# NixieTerm.net
KiCad netlist of a schematic drawn in EAGLE
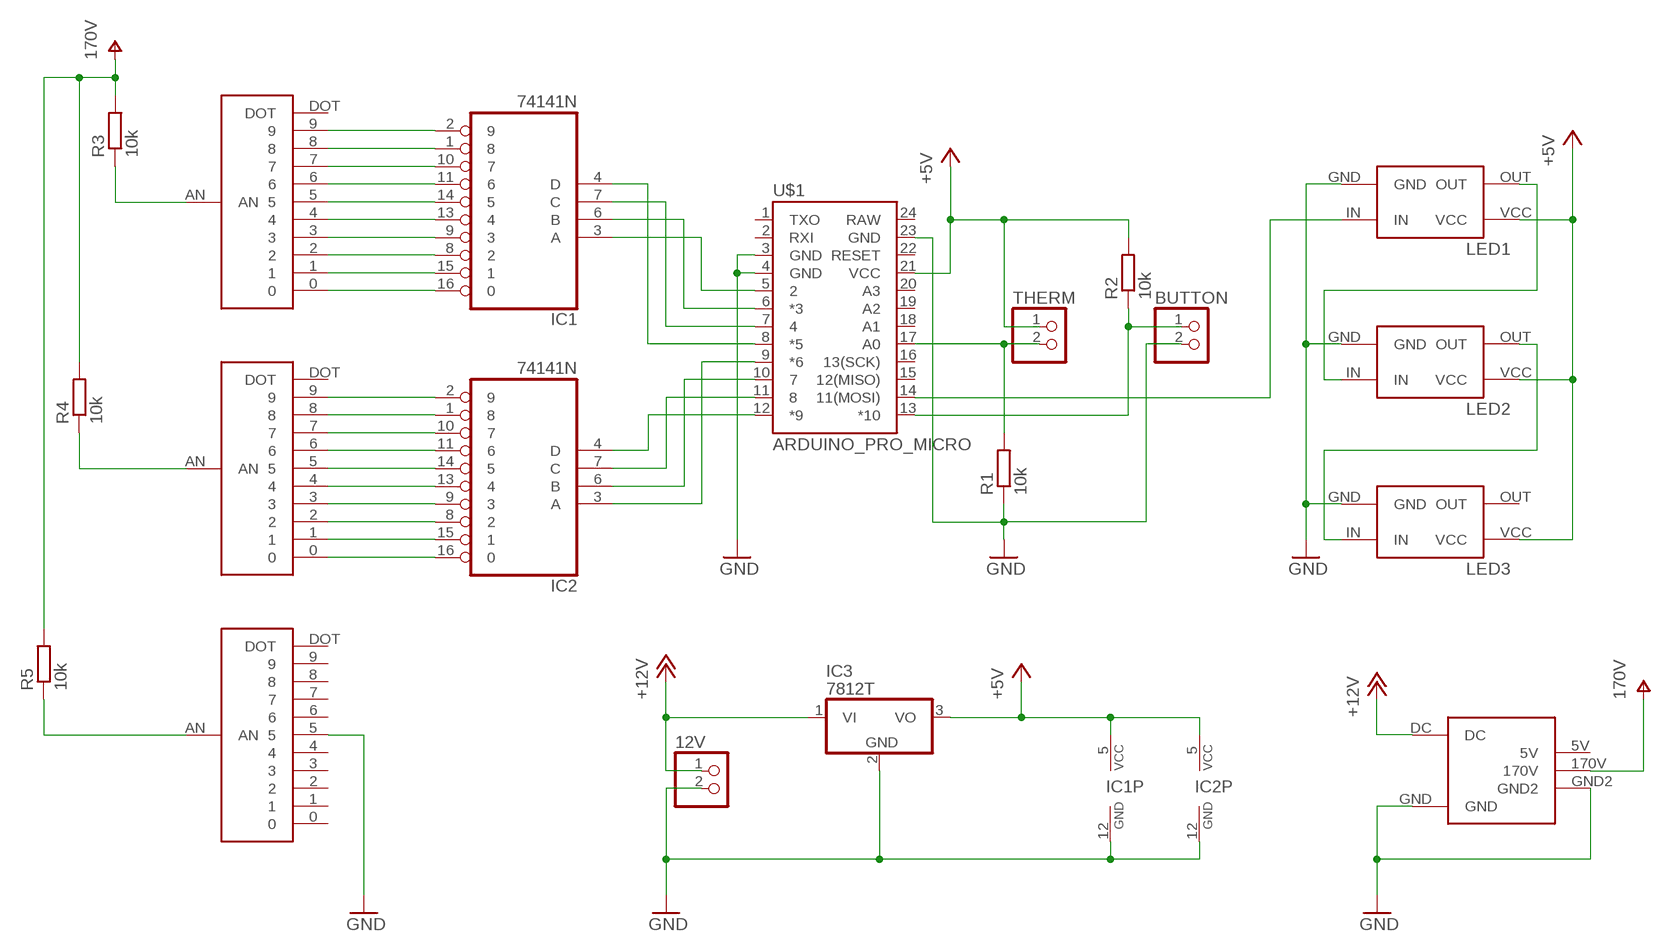
[diagram p0: schematic, sheet 1]

(export (version "E")
  (design (tool "Eeschema 10.0.6"))
  (components
    (comp (ref "12V")
      (value "PINHD-1X2")
      (footprint "eagle-import:1X02")
      (libsource (lib "eagle-import") (part "PINHD-1X2"))
    )
    (comp (ref "BUTTON")
      (value "PINHD-1X2")
      (footprint "eagle-import:1X02")
      (libsource (lib "eagle-import") (part "PINHD-1X2"))
    )
    (comp (ref "DEC")
      (value "NIXIE-SOCKET")
      (footprint "eagle-import:NIXIE-SOCKET-PAC")
      (libsource (lib "eagle-import") (part "NIXIE-SOCKET"))
    )
    (comp (ref "IC1")
      (value "74141N")
      (footprint "eagle-import:DIL16")
      (libsource (lib "eagle-import") (part "74141N"))
    )
    (comp (ref "IC2")
      (value "74141N")
      (footprint "eagle-import:DIL16")
      (libsource (lib "eagle-import") (part "74141N"))
    )
    (comp (ref "IC3")
      (value "7812T")
      (footprint "eagle-import:TO220H")
      (libsource (lib "eagle-import") (part "78T12"))
    )
    (comp (ref "LED1")
      (value "WS2812-LED")
      (footprint "eagle-import:WS2812-LED-PAC")
      (libsource (lib "eagle-import") (part "WS2812-LED"))
    )
    (comp (ref "LED2")
      (value "WS2812-LED")
      (footprint "eagle-import:WS2812-LED-PAC")
      (libsource (lib "eagle-import") (part "WS2812-LED"))
    )
    (comp (ref "LED3")
      (value "WS2812-LED")
      (footprint "eagle-import:WS2812-LED-PAC")
      (libsource (lib "eagle-import") (part "WS2812-LED"))
    )
    (comp (ref "R1")
      (value "10k")
      (footprint "eagle-import:0207_12")
      (libsource (lib "eagle-import") (part "R-EU_0207/12"))
    )
    (comp (ref "R2")
      (value "10k")
      (footprint "eagle-import:0207_12")
      (libsource (lib "eagle-import") (part "R-EU_0207/12"))
    )
    (comp (ref "R3")
      (value "10k")
      (footprint "eagle-import:0207_12")
      (libsource (lib "eagle-import") (part "R-EU_0207/12"))
    )
    (comp (ref "R4")
      (value "10k")
      (footprint "eagle-import:0207_12")
      (libsource (lib "eagle-import") (part "R-EU_0207/12"))
    )
    (comp (ref "R5")
      (value "10k")
      (footprint "eagle-import:0207_12")
      (libsource (lib "eagle-import") (part "R-EU_0207/12"))
    )
    (comp (ref "SYM")
      (value "NIXIE-SOCKET")
      (footprint "eagle-import:NIXIE-SOCKET-PAC")
      (libsource (lib "eagle-import") (part "NIXIE-SOCKET"))
    )
    (comp (ref "THERM")
      (value "PINHD-1X2")
      (footprint "eagle-import:1X02")
      (libsource (lib "eagle-import") (part "PINHD-1X2"))
    )
    (comp (ref "U$1")
      (value "ARDUINO_PRO_MICRO")
      (footprint "eagle-import:ARDUINO_PRO_MICRO")
      (libsource (lib "eagle-import") (part "ARDUINO_PRO_MICRO"))
    )
    (comp (ref "U$2")
      (value "NIXIE-SUPPLY")
      (footprint "eagle-import:NIXIE-SUPPLY-PAC")
      (libsource (lib "eagle-import") (part "NIXIE-SUPPLY"))
    )
    (comp (ref "UNIT")
      (value "NIXIE-SOCKET")
      (footprint "eagle-import:NIXIE-SOCKET-PAC")
      (libsource (lib "eagle-import") (part "NIXIE-SOCKET"))
    )
  )
  (nets
    (net (code "1") (name "+5V") (class "Default")
      (node (ref "IC1") (pin "5") (pinfunction "VCC_5") (pintype "power_in"))
      (node (ref "IC2") (pin "5") (pinfunction "VCC_5") (pintype "power_in"))
      (node (ref "IC3") (pin "3") (pinfunction "VO_3") (pintype "passive"))
      (node (ref "LED1") (pin "VCC") (pinfunction "VCC_VCC") (pintype "bidirectional"))
      (node (ref "LED2") (pin "VCC") (pinfunction "VCC_VCC") (pintype "bidirectional"))
      (node (ref "LED3") (pin "VCC") (pinfunction "VCC_VCC") (pintype "bidirectional"))
      (node (ref "R2") (pin "2") (pinfunction "2_2") (pintype "passive"))
      (node (ref "THERM") (pin "1") (pinfunction "1_1") (pintype "passive"))
      (node (ref "U$1") (pin "21") (pinfunction "VCC_21") (pintype "bidirectional"))
    )
    (net (code "2") (name "+12V") (class "Default")
      (node (ref "12V") (pin "1") (pinfunction "1_1") (pintype "passive"))
      (node (ref "IC3") (pin "1") (pinfunction "VI_1") (pintype "input"))
      (node (ref "U$2") (pin "DC") (pinfunction "DC_DC") (pintype "bidirectional"))
    )
    (net (code "3") (name "170V") (class "Default")
      (node (ref "R3") (pin "2") (pinfunction "2_2") (pintype "passive"))
      (node (ref "R4") (pin "2") (pinfunction "2_2") (pintype "passive"))
      (node (ref "R5") (pin "2") (pinfunction "2_2") (pintype "passive"))
      (node (ref "U$2") (pin "170V") (pinfunction "170V_170V") (pintype "bidirectional"))
    )
    (net (code "4") (name "GND") (class "Default")
      (node (ref "12V") (pin "2") (pinfunction "2_2") (pintype "passive"))
      (node (ref "BUTTON") (pin "2") (pinfunction "2_2") (pintype "passive"))
      (node (ref "IC1") (pin "12") (pinfunction "GND_12") (pintype "power_in"))
      (node (ref "IC2") (pin "12") (pinfunction "GND_12") (pintype "power_in"))
      (node (ref "IC3") (pin "2") (pinfunction "GND_2") (pintype "passive"))
      (node (ref "LED1") (pin "GND") (pinfunction "GND_GND") (pintype "bidirectional"))
      (node (ref "LED2") (pin "GND") (pinfunction "GND_GND") (pintype "bidirectional"))
      (node (ref "LED3") (pin "GND") (pinfunction "GND_GND") (pintype "bidirectional"))
      (node (ref "R1") (pin "1") (pinfunction "1_1") (pintype "passive"))
      (node (ref "SYM") (pin "5") (pinfunction "5_5") (pintype "bidirectional"))
      (node (ref "U$1") (pin "23") (pinfunction "GND_23") (pintype "bidirectional"))
      (node (ref "U$1") (pin "3") (pinfunction "GND_3") (pintype "bidirectional"))
      (node (ref "U$1") (pin "4") (pinfunction "GND_4") (pintype "bidirectional"))
      (node (ref "U$2") (pin "GND") (pinfunction "GND_GND") (pintype "bidirectional"))
      (node (ref "U$2") (pin "GND2") (pinfunction "GND2_GND2") (pintype "bidirectional"))
    )
    (net (code "5") (name "Net-(DEC-PadAN)") (class "Default")
      (node (ref "DEC") (pin "AN") (pinfunction "AN_AN") (pintype "bidirectional"))
      (node (ref "R3") (pin "1") (pinfunction "1_1") (pintype "passive"))
    )
    (net (code "6") (name "Net-(IC1A-0)") (class "Default")
      (node (ref "DEC") (pin "0") (pinfunction "0_0") (pintype "bidirectional"))
      (node (ref "IC1") (pin "16") (pinfunction "0_16") (pintype "open_collector"))
    )
    (net (code "7") (name "Net-(IC1A-1)") (class "Default")
      (node (ref "DEC") (pin "1") (pinfunction "1_1") (pintype "bidirectional"))
      (node (ref "IC1") (pin "15") (pinfunction "1_15") (pintype "open_collector"))
    )
    (net (code "8") (name "Net-(IC1A-2)") (class "Default")
      (node (ref "DEC") (pin "2") (pinfunction "2_2") (pintype "bidirectional"))
      (node (ref "IC1") (pin "8") (pinfunction "2_8") (pintype "open_collector"))
    )
    (net (code "9") (name "Net-(IC1A-3)") (class "Default")
      (node (ref "DEC") (pin "3") (pinfunction "3_3") (pintype "bidirectional"))
      (node (ref "IC1") (pin "9") (pinfunction "3_9") (pintype "open_collector"))
    )
    (net (code "10") (name "Net-(IC1A-4)") (class "Default")
      (node (ref "DEC") (pin "4") (pinfunction "4_4") (pintype "bidirectional"))
      (node (ref "IC1") (pin "13") (pinfunction "4_13") (pintype "open_collector"))
    )
    (net (code "11") (name "Net-(IC1A-5)") (class "Default")
      (node (ref "DEC") (pin "5") (pinfunction "5_5") (pintype "bidirectional"))
      (node (ref "IC1") (pin "14") (pinfunction "5_14") (pintype "open_collector"))
    )
    (net (code "12") (name "Net-(IC1A-6)") (class "Default")
      (node (ref "DEC") (pin "6") (pinfunction "6_6") (pintype "bidirectional"))
      (node (ref "IC1") (pin "11") (pinfunction "6_11") (pintype "open_collector"))
    )
    (net (code "13") (name "Net-(IC1A-7)") (class "Default")
      (node (ref "DEC") (pin "7") (pinfunction "7_7") (pintype "bidirectional"))
      (node (ref "IC1") (pin "10") (pinfunction "7_10") (pintype "open_collector"))
    )
    (net (code "14") (name "Net-(IC1A-8)") (class "Default")
      (node (ref "DEC") (pin "8") (pinfunction "8_8") (pintype "bidirectional"))
      (node (ref "IC1") (pin "1") (pinfunction "8_1") (pintype "open_collector"))
    )
    (net (code "15") (name "Net-(IC1A-9)") (class "Default")
      (node (ref "DEC") (pin "9") (pinfunction "9_9") (pintype "bidirectional"))
      (node (ref "IC1") (pin "2") (pinfunction "9_2") (pintype "open_collector"))
    )
    (net (code "16") (name "Net-(IC1A-A)") (class "Default")
      (node (ref "IC1") (pin "3") (pinfunction "A_3") (pintype "input"))
      (node (ref "U$1") (pin "5") (pinfunction "2_5") (pintype "bidirectional"))
    )
    (net (code "17") (name "Net-(IC1A-B)") (class "Default")
      (node (ref "IC1") (pin "6") (pinfunction "B_6") (pintype "input"))
      (node (ref "U$1") (pin "6") (pinfunction "*3_6") (pintype "bidirectional"))
    )
    (net (code "18") (name "Net-(IC1A-C)") (class "Default")
      (node (ref "IC1") (pin "7") (pinfunction "C_7") (pintype "input"))
      (node (ref "U$1") (pin "7") (pinfunction "4_7") (pintype "bidirectional"))
    )
    (net (code "19") (name "Net-(IC1A-D)") (class "Default")
      (node (ref "IC1") (pin "4") (pinfunction "D_4") (pintype "input"))
      (node (ref "U$1") (pin "8") (pinfunction "*5_8") (pintype "bidirectional"))
    )
    (net (code "20") (name "Net-(IC2A-0)") (class "Default")
      (node (ref "IC2") (pin "16") (pinfunction "0_16") (pintype "open_collector"))
      (node (ref "UNIT") (pin "0") (pinfunction "0_0") (pintype "bidirectional"))
    )
    (net (code "21") (name "Net-(IC2A-1)") (class "Default")
      (node (ref "IC2") (pin "15") (pinfunction "1_15") (pintype "open_collector"))
      (node (ref "UNIT") (pin "1") (pinfunction "1_1") (pintype "bidirectional"))
    )
    (net (code "22") (name "Net-(IC2A-2)") (class "Default")
      (node (ref "IC2") (pin "8") (pinfunction "2_8") (pintype "open_collector"))
      (node (ref "UNIT") (pin "2") (pinfunction "2_2") (pintype "bidirectional"))
    )
    (net (code "23") (name "Net-(IC2A-3)") (class "Default")
      (node (ref "IC2") (pin "9") (pinfunction "3_9") (pintype "open_collector"))
      (node (ref "UNIT") (pin "3") (pinfunction "3_3") (pintype "bidirectional"))
    )
    (net (code "24") (name "Net-(IC2A-4)") (class "Default")
      (node (ref "IC2") (pin "13") (pinfunction "4_13") (pintype "open_collector"))
      (node (ref "UNIT") (pin "4") (pinfunction "4_4") (pintype "bidirectional"))
    )
    (net (code "25") (name "Net-(IC2A-5)") (class "Default")
      (node (ref "IC2") (pin "14") (pinfunction "5_14") (pintype "open_collector"))
      (node (ref "UNIT") (pin "5") (pinfunction "5_5") (pintype "bidirectional"))
    )
    (net (code "26") (name "Net-(IC2A-6)") (class "Default")
      (node (ref "IC2") (pin "11") (pinfunction "6_11") (pintype "open_collector"))
      (node (ref "UNIT") (pin "6") (pinfunction "6_6") (pintype "bidirectional"))
    )
    (net (code "27") (name "Net-(IC2A-7)") (class "Default")
      (node (ref "IC2") (pin "10") (pinfunction "7_10") (pintype "open_collector"))
      (node (ref "UNIT") (pin "7") (pinfunction "7_7") (pintype "bidirectional"))
    )
    (net (code "28") (name "Net-(IC2A-8)") (class "Default")
      (node (ref "IC2") (pin "1") (pinfunction "8_1") (pintype "open_collector"))
      (node (ref "UNIT") (pin "8") (pinfunction "8_8") (pintype "bidirectional"))
    )
    (net (code "29") (name "Net-(IC2A-9)") (class "Default")
      (node (ref "IC2") (pin "2") (pinfunction "9_2") (pintype "open_collector"))
      (node (ref "UNIT") (pin "9") (pinfunction "9_9") (pintype "bidirectional"))
    )
    (net (code "30") (name "Net-(IC2A-A)") (class "Default")
      (node (ref "IC2") (pin "3") (pinfunction "A_3") (pintype "input"))
      (node (ref "U$1") (pin "9") (pinfunction "*6_9") (pintype "bidirectional"))
    )
    (net (code "31") (name "Net-(IC2A-B)") (class "Default")
      (node (ref "IC2") (pin "6") (pinfunction "B_6") (pintype "input"))
      (node (ref "U$1") (pin "10") (pinfunction "7_10") (pintype "bidirectional"))
    )
    (net (code "32") (name "Net-(IC2A-C)") (class "Default")
      (node (ref "IC2") (pin "7") (pinfunction "C_7") (pintype "input"))
      (node (ref "U$1") (pin "11") (pinfunction "8_11") (pintype "bidirectional"))
    )
    (net (code "33") (name "Net-(IC2A-D)") (class "Default")
      (node (ref "IC2") (pin "4") (pinfunction "D_4") (pintype "input"))
      (node (ref "U$1") (pin "12") (pinfunction "*9_12") (pintype "bidirectional"))
    )
    (net (code "34") (name "Net-(LED1-PadOUT)") (class "Default")
      (node (ref "LED1") (pin "OUT") (pinfunction "OUT_OUT") (pintype "bidirectional"))
      (node (ref "LED2") (pin "IN") (pinfunction "IN_IN") (pintype "bidirectional"))
    )
    (net (code "35") (name "Net-(LED2-PadOUT)") (class "Default")
      (node (ref "LED2") (pin "OUT") (pinfunction "OUT_OUT") (pintype "bidirectional"))
      (node (ref "LED3") (pin "IN") (pinfunction "IN_IN") (pintype "bidirectional"))
    )
    (net (code "36") (name "Net-(R4-Pad1)") (class "Default")
      (node (ref "R4") (pin "1") (pinfunction "1_1") (pintype "passive"))
      (node (ref "UNIT") (pin "AN") (pinfunction "AN_AN") (pintype "bidirectional"))
    )
    (net (code "37") (name "Net-(R5-Pad1)") (class "Default")
      (node (ref "R5") (pin "1") (pinfunction "1_1") (pintype "passive"))
      (node (ref "SYM") (pin "AN") (pinfunction "AN_AN") (pintype "bidirectional"))
    )
    (net (code "38") (name "Net-(U$1-*10)") (class "Default")
      (node (ref "BUTTON") (pin "1") (pinfunction "1_1") (pintype "passive"))
      (node (ref "R2") (pin "1") (pinfunction "1_1") (pintype "passive"))
      (node (ref "U$1") (pin "13") (pinfunction "*10_13") (pintype "bidirectional"))
    )
    (net (code "39") (name "Net-(U$1-11(MOSI))") (class "Default")
      (node (ref "LED1") (pin "IN") (pinfunction "IN_IN") (pintype "bidirectional"))
      (node (ref "U$1") (pin "14") (pinfunction "11(MOSI)_14") (pintype "bidirectional"))
    )
    (net (code "40") (name "Net-(U$1-A0)") (class "Default")
      (node (ref "R1") (pin "2") (pinfunction "2_2") (pintype "passive"))
      (node (ref "THERM") (pin "2") (pinfunction "2_2") (pintype "passive"))
      (node (ref "U$1") (pin "17") (pinfunction "A0_17") (pintype "bidirectional"))
    )
    (net (code "41") (name "unconnected-(DEC-PadDOT)") (class "Default")
      (node (ref "DEC") (pin "DOT") (pinfunction "DOT_DOT") (pintype "bidirectional"))
    )
    (net (code "42") (name "unconnected-(LED3-PadOUT)") (class "Default")
      (node (ref "LED3") (pin "OUT") (pinfunction "OUT_OUT") (pintype "bidirectional"))
    )
    (net (code "43") (name "unconnected-(SYM-Pad0)") (class "Default")
      (node (ref "SYM") (pin "0") (pinfunction "0_0") (pintype "bidirectional"))
    )
    (net (code "44") (name "unconnected-(SYM-Pad1)") (class "Default")
      (node (ref "SYM") (pin "1") (pinfunction "1_1") (pintype "bidirectional"))
    )
    (net (code "45") (name "unconnected-(SYM-Pad2)") (class "Default")
      (node (ref "SYM") (pin "2") (pinfunction "2_2") (pintype "bidirectional"))
    )
    (net (code "46") (name "unconnected-(SYM-Pad3)") (class "Default")
      (node (ref "SYM") (pin "3") (pinfunction "3_3") (pintype "bidirectional"))
    )
    (net (code "47") (name "unconnected-(SYM-Pad4)") (class "Default")
      (node (ref "SYM") (pin "4") (pinfunction "4_4") (pintype "bidirectional"))
    )
    (net (code "48") (name "unconnected-(SYM-Pad6)") (class "Default")
      (node (ref "SYM") (pin "6") (pinfunction "6_6") (pintype "bidirectional"))
    )
    (net (code "49") (name "unconnected-(SYM-Pad7)") (class "Default")
      (node (ref "SYM") (pin "7") (pinfunction "7_7") (pintype "bidirectional"))
    )
    (net (code "50") (name "unconnected-(SYM-Pad8)") (class "Default")
      (node (ref "SYM") (pin "8") (pinfunction "8_8") (pintype "bidirectional"))
    )
    (net (code "51") (name "unconnected-(SYM-Pad9)") (class "Default")
      (node (ref "SYM") (pin "9") (pinfunction "9_9") (pintype "bidirectional"))
    )
    (net (code "52") (name "unconnected-(SYM-PadDOT)") (class "Default")
      (node (ref "SYM") (pin "DOT") (pinfunction "DOT_DOT") (pintype "bidirectional"))
    )
    (net (code "53") (name "unconnected-(U$1-12(MISO)-Pad15)") (class "Default")
      (node (ref "U$1") (pin "15") (pinfunction "12(MISO)_15") (pintype "bidirectional"))
    )
    (net (code "54") (name "unconnected-(U$1-13(SCK)-Pad16)") (class "Default")
      (node (ref "U$1") (pin "16") (pinfunction "13(SCK)_16") (pintype "bidirectional"))
    )
    (net (code "55") (name "unconnected-(U$1-A1-Pad18)") (class "Default")
      (node (ref "U$1") (pin "18") (pinfunction "A1_18") (pintype "bidirectional"))
    )
    (net (code "56") (name "unconnected-(U$1-A2-Pad19)") (class "Default")
      (node (ref "U$1") (pin "19") (pinfunction "A2_19") (pintype "bidirectional"))
    )
    (net (code "57") (name "unconnected-(U$1-A3-Pad20)") (class "Default")
      (node (ref "U$1") (pin "20") (pinfunction "A3_20") (pintype "bidirectional"))
    )
    (net (code "58") (name "unconnected-(U$1-RAW-Pad24)") (class "Default")
      (node (ref "U$1") (pin "24") (pinfunction "RAW_24") (pintype "bidirectional"))
    )
    (net (code "59") (name "unconnected-(U$1-RESET-Pad22)") (class "Default")
      (node (ref "U$1") (pin "22") (pinfunction "RESET_22") (pintype "bidirectional"))
    )
    (net (code "60") (name "unconnected-(U$1-RXI-Pad2)") (class "Default")
      (node (ref "U$1") (pin "2") (pinfunction "RXI_2") (pintype "bidirectional"))
    )
    (net (code "61") (name "unconnected-(U$1-TXO-Pad1)") (class "Default")
      (node (ref "U$1") (pin "1") (pinfunction "TXO_1") (pintype "bidirectional"))
    )
    (net (code "62") (name "unconnected-(U$2-Pad5V)") (class "Default")
      (node (ref "U$2") (pin "5V") (pinfunction "5V_5V") (pintype "bidirectional"))
    )
    (net (code "63") (name "unconnected-(UNIT-PadDOT)") (class "Default")
      (node (ref "UNIT") (pin "DOT") (pinfunction "DOT_DOT") (pintype "bidirectional"))
    )
  )
)
